# smartcar_shield_cutouts.net
KiCad netlist of a schematic drawn in EAGLE
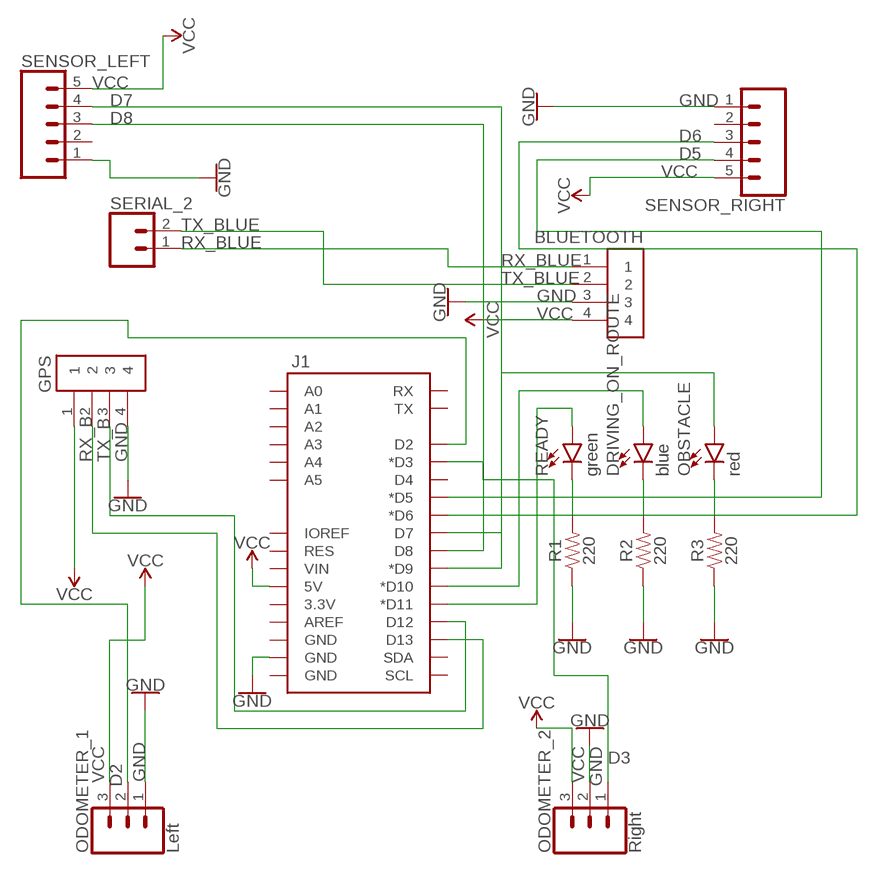
[diagram p0: schematic, sheet 1]

(export (version "E")
  (design (tool "Eeschema 10.0.6"))
  (components
    (comp (ref "BLUETOOTH")
      (value "1X4-BIG")
      (footprint "eagle-import:1X04-BIG")
      (libsource (lib "eagle-import") (part "1X4-BIG"))
    )
    (comp (ref "DRIVING_ON_ROUTE")
      (value "blue")
      (footprint "eagle-import:LED_5MM")
      (libsource (lib "eagle-import") (part "LED5MM"))
    )
    (comp (ref "GPS")
      (value "1X4-BIG")
      (footprint "eagle-import:1X04-BIG")
      (libsource (lib "eagle-import") (part "1X4-BIG"))
    )
    (comp (ref "J1")
      (value "ARDUINO_R3_SHIELDUNO_R3_SHIELD_LOCK")
      (footprint "eagle-import:UNO_R3_SHIELD_LOCK")
      (libsource (lib "eagle-import") (part "ARDUINO_R3_SHIELDUNO_R3_SHIELD_LOCK"))
    )
    (comp (ref "OBSTACLE")
      (value "red")
      (footprint "eagle-import:LED_5MM")
      (libsource (lib "eagle-import") (part "LED5MM"))
    )
    (comp (ref "ODOMETER_1")
      (value "Left")
      (footprint "eagle-import:1X03")
      (libsource (lib "eagle-import") (part "CONN_03"))
    )
    (comp (ref "ODOMETER_2")
      (value "Right")
      (footprint "eagle-import:1X03")
      (libsource (lib "eagle-import") (part "CONN_03"))
    )
    (comp (ref "R1")
      (value "220")
      (footprint "eagle-import:0603")
      (libsource (lib "eagle-import") (part "220OHM-0603-1/10W-1%"))
    )
    (comp (ref "R2")
      (value "220")
      (footprint "eagle-import:0603")
      (libsource (lib "eagle-import") (part "220OHM-0603-1/10W-1%"))
    )
    (comp (ref "R3")
      (value "220")
      (footprint "eagle-import:0603")
      (libsource (lib "eagle-import") (part "220OHM-0603-1/10W-1%"))
    )
    (comp (ref "READY")
      (value "green")
      (footprint "eagle-import:LED_5MM")
      (libsource (lib "eagle-import") (part "LED5MM"))
    )
    (comp (ref "SENSOR_LEFT")
      (value "CONN_05")
      (footprint "eagle-import:1X05")
      (libsource (lib "eagle-import") (part "CONN_05"))
    )
    (comp (ref "SENSOR_RIGHT")
      (value "CONN_05")
      (footprint "eagle-import:1X05")
      (libsource (lib "eagle-import") (part "CONN_05"))
    )
    (comp (ref "SERIAL_2")
      (value "CONN_02")
      (footprint "eagle-import:1X02")
      (libsource (lib "eagle-import") (part "CONN_02"))
    )
  )
  (nets
    (net (code "1") (name "/D2") (class "Default")
      (node (ref "J1") (pin "D2") (pinfunction "D2_D2") (pintype "bidirectional"))
      (node (ref "ODOMETER_1") (pin "2") (pinfunction "2_2") (pintype "passive"))
    )
    (net (code "2") (name "/D3") (class "Default")
      (node (ref "J1") (pin "D3") (pinfunction "*D3_D3") (pintype "bidirectional"))
      (node (ref "ODOMETER_2") (pin "1") (pinfunction "1_1") (pintype "passive"))
    )
    (net (code "3") (name "/D5") (class "Default")
      (node (ref "J1") (pin "D5") (pinfunction "*D5_D5") (pintype "bidirectional"))
      (node (ref "SENSOR_RIGHT") (pin "4") (pinfunction "4_4") (pintype "passive"))
    )
    (net (code "4") (name "/D6") (class "Default")
      (node (ref "J1") (pin "D6") (pinfunction "*D6_D6") (pintype "bidirectional"))
      (node (ref "SENSOR_RIGHT") (pin "3") (pinfunction "3_3") (pintype "passive"))
    )
    (net (code "5") (name "/D7") (class "Default")
      (node (ref "J1") (pin "D7") (pinfunction "D7_D7") (pintype "bidirectional"))
      (node (ref "SENSOR_LEFT") (pin "4") (pinfunction "4_4") (pintype "passive"))
    )
    (net (code "6") (name "/D8") (class "Default")
      (node (ref "J1") (pin "D8") (pinfunction "D8_D8") (pintype "bidirectional"))
      (node (ref "SENSOR_LEFT") (pin "3") (pinfunction "3_3") (pintype "passive"))
    )
    (net (code "7") (name "/RX_B") (class "Default")
      (node (ref "GPS") (pin "2") (pinfunction "2_2") (pintype "bidirectional"))
      (node (ref "J1") (pin "D13") (pinfunction "D13_D13") (pintype "bidirectional"))
    )
    (net (code "8") (name "/RX_BLUE") (class "Default")
      (node (ref "BLUETOOTH") (pin "1") (pinfunction "1_1") (pintype "bidirectional"))
      (node (ref "SERIAL_2") (pin "1") (pinfunction "1_1") (pintype "passive"))
    )
    (net (code "9") (name "/TX_B") (class "Default")
      (node (ref "GPS") (pin "3") (pinfunction "3_3") (pintype "bidirectional"))
      (node (ref "J1") (pin "D12") (pinfunction "D12_D12") (pintype "bidirectional"))
    )
    (net (code "10") (name "/TX_BLUE") (class "Default")
      (node (ref "BLUETOOTH") (pin "2") (pinfunction "2_2") (pintype "bidirectional"))
      (node (ref "SERIAL_2") (pin "2") (pinfunction "2_2") (pintype "passive"))
    )
    (net (code "11") (name "GND") (class "Default")
      (node (ref "BLUETOOTH") (pin "3") (pinfunction "3_3") (pintype "bidirectional"))
      (node (ref "GPS") (pin "4") (pinfunction "4_4") (pintype "bidirectional"))
      (node (ref "J1") (pin "GND@1") (pinfunction "GND_GND@1") (pintype "bidirectional"))
      (node (ref "ODOMETER_1") (pin "1") (pinfunction "1_1") (pintype "passive"))
      (node (ref "ODOMETER_2") (pin "2") (pinfunction "2_2") (pintype "passive"))
      (node (ref "R1") (pin "1") (pinfunction "1_1") (pintype "passive"))
      (node (ref "R2") (pin "1") (pinfunction "1_1") (pintype "passive"))
      (node (ref "R3") (pin "1") (pinfunction "1_1") (pintype "passive"))
      (node (ref "SENSOR_LEFT") (pin "1") (pinfunction "1_1") (pintype "passive"))
      (node (ref "SENSOR_RIGHT") (pin "1") (pinfunction "1_1") (pintype "passive"))
    )
    (net (code "12") (name "Net-(DRIVING_ON_ROUTE-C)") (class "Default")
      (node (ref "DRIVING_ON_ROUTE") (pin "K") (pinfunction "C_K") (pintype "passive"))
      (node (ref "R2") (pin "2") (pinfunction "2_2") (pintype "passive"))
    )
    (net (code "13") (name "Net-(J1-*D9)") (class "Default")
      (node (ref "J1") (pin "D9") (pinfunction "*D9_D9") (pintype "bidirectional"))
      (node (ref "OBSTACLE") (pin "A") (pinfunction "A_A") (pintype "passive"))
    )
    (net (code "14") (name "Net-(J1-*D10)") (class "Default")
      (node (ref "DRIVING_ON_ROUTE") (pin "A") (pinfunction "A_A") (pintype "passive"))
      (node (ref "J1") (pin "D10") (pinfunction "*D10_D10") (pintype "bidirectional"))
    )
    (net (code "15") (name "Net-(J1-*D11)") (class "Default")
      (node (ref "J1") (pin "D11") (pinfunction "*D11_D11") (pintype "bidirectional"))
      (node (ref "READY") (pin "A") (pinfunction "A_A") (pintype "passive"))
    )
    (net (code "16") (name "Net-(OBSTACLE-C)") (class "Default")
      (node (ref "OBSTACLE") (pin "K") (pinfunction "C_K") (pintype "passive"))
      (node (ref "R3") (pin "2") (pinfunction "2_2") (pintype "passive"))
    )
    (net (code "17") (name "Net-(READY-C)") (class "Default")
      (node (ref "R1") (pin "2") (pinfunction "2_2") (pintype "passive"))
      (node (ref "READY") (pin "K") (pinfunction "C_K") (pintype "passive"))
    )
    (net (code "18") (name "VCC") (class "Default")
      (node (ref "BLUETOOTH") (pin "4") (pinfunction "4_4") (pintype "bidirectional"))
      (node (ref "GPS") (pin "1") (pinfunction "1_1") (pintype "bidirectional"))
      (node (ref "J1") (pin "5V") (pinfunction "5V_5V") (pintype "bidirectional"))
      (node (ref "ODOMETER_1") (pin "3") (pinfunction "3_3") (pintype "passive"))
      (node (ref "ODOMETER_2") (pin "3") (pinfunction "3_3") (pintype "passive"))
      (node (ref "SENSOR_LEFT") (pin "5") (pinfunction "5_5") (pintype "passive"))
      (node (ref "SENSOR_RIGHT") (pin "5") (pinfunction "5_5") (pintype "passive"))
    )
    (net (code "19") (name "unconnected-(J1-GND-PadGND@0)") (class "Default")
      (node (ref "J1") (pin "GND@0") (pinfunction "GND_GND@0") (pintype "bidirectional"))
    )
    (net (code "20") (name "unconnected-(J1-GND-PadGND@2)") (class "Default")
      (node (ref "J1") (pin "GND@2") (pinfunction "GND_GND@2") (pintype "bidirectional"))
    )
    (net (code "21") (name "unconnected-(J1-Pad3.3V)") (class "Default")
      (node (ref "J1") (pin "3.3V") (pinfunction "3.3V_3.3V") (pintype "bidirectional"))
    )
    (net (code "22") (name "unconnected-(J1-PadA0)") (class "Default")
      (node (ref "J1") (pin "A0") (pinfunction "A0_A0") (pintype "bidirectional"))
    )
    (net (code "23") (name "unconnected-(J1-PadA1)") (class "Default")
      (node (ref "J1") (pin "A1") (pinfunction "A1_A1") (pintype "bidirectional"))
    )
    (net (code "24") (name "unconnected-(J1-PadA2)") (class "Default")
      (node (ref "J1") (pin "A2") (pinfunction "A2_A2") (pintype "bidirectional"))
    )
    (net (code "25") (name "unconnected-(J1-PadA3)") (class "Default")
      (node (ref "J1") (pin "A3") (pinfunction "A3_A3") (pintype "bidirectional"))
    )
    (net (code "26") (name "unconnected-(J1-PadA4)") (class "Default")
      (node (ref "J1") (pin "A4") (pinfunction "A4_A4") (pintype "bidirectional"))
    )
    (net (code "27") (name "unconnected-(J1-PadA5)") (class "Default")
      (node (ref "J1") (pin "A5") (pinfunction "A5_A5") (pintype "bidirectional"))
    )
    (net (code "28") (name "unconnected-(J1-PadAREF)") (class "Default")
      (node (ref "J1") (pin "AREF") (pinfunction "AREF_AREF") (pintype "bidirectional"))
    )
    (net (code "29") (name "unconnected-(J1-PadD4)") (class "Default")
      (node (ref "J1") (pin "D4") (pinfunction "D4_D4") (pintype "bidirectional"))
    )
    (net (code "30") (name "unconnected-(J1-PadIOREF)") (class "Default")
      (node (ref "J1") (pin "IOREF") (pinfunction "IOREF_IOREF") (pintype "bidirectional"))
    )
    (net (code "31") (name "unconnected-(J1-PadRES)") (class "Default")
      (node (ref "J1") (pin "RES") (pinfunction "RES_RES") (pintype "bidirectional"))
    )
    (net (code "32") (name "unconnected-(J1-PadRX)") (class "Default")
      (node (ref "J1") (pin "RX") (pinfunction "RX_RX") (pintype "bidirectional"))
    )
    (net (code "33") (name "unconnected-(J1-PadSCL)") (class "Default")
      (node (ref "J1") (pin "SCL") (pinfunction "SCL_SCL") (pintype "bidirectional"))
    )
    (net (code "34") (name "unconnected-(J1-PadSDA)") (class "Default")
      (node (ref "J1") (pin "SDA") (pinfunction "SDA_SDA") (pintype "bidirectional"))
    )
    (net (code "35") (name "unconnected-(J1-PadTX)") (class "Default")
      (node (ref "J1") (pin "TX") (pinfunction "TX_TX") (pintype "bidirectional"))
    )
    (net (code "36") (name "unconnected-(J1-PadVIN)") (class "Default")
      (node (ref "J1") (pin "VIN") (pinfunction "VIN_VIN") (pintype "bidirectional"))
    )
    (net (code "37") (name "unconnected-(SENSOR_LEFT-Pad2)") (class "Default")
      (node (ref "SENSOR_LEFT") (pin "2") (pinfunction "2_2") (pintype "passive"))
    )
    (net (code "38") (name "unconnected-(SENSOR_RIGHT-Pad2)") (class "Default")
      (node (ref "SENSOR_RIGHT") (pin "2") (pinfunction "2_2") (pintype "passive"))
    )
  )
)
